# 20x20_adapter_rush_v2.net
KiCad netlist of a schematic drawn in EAGLE
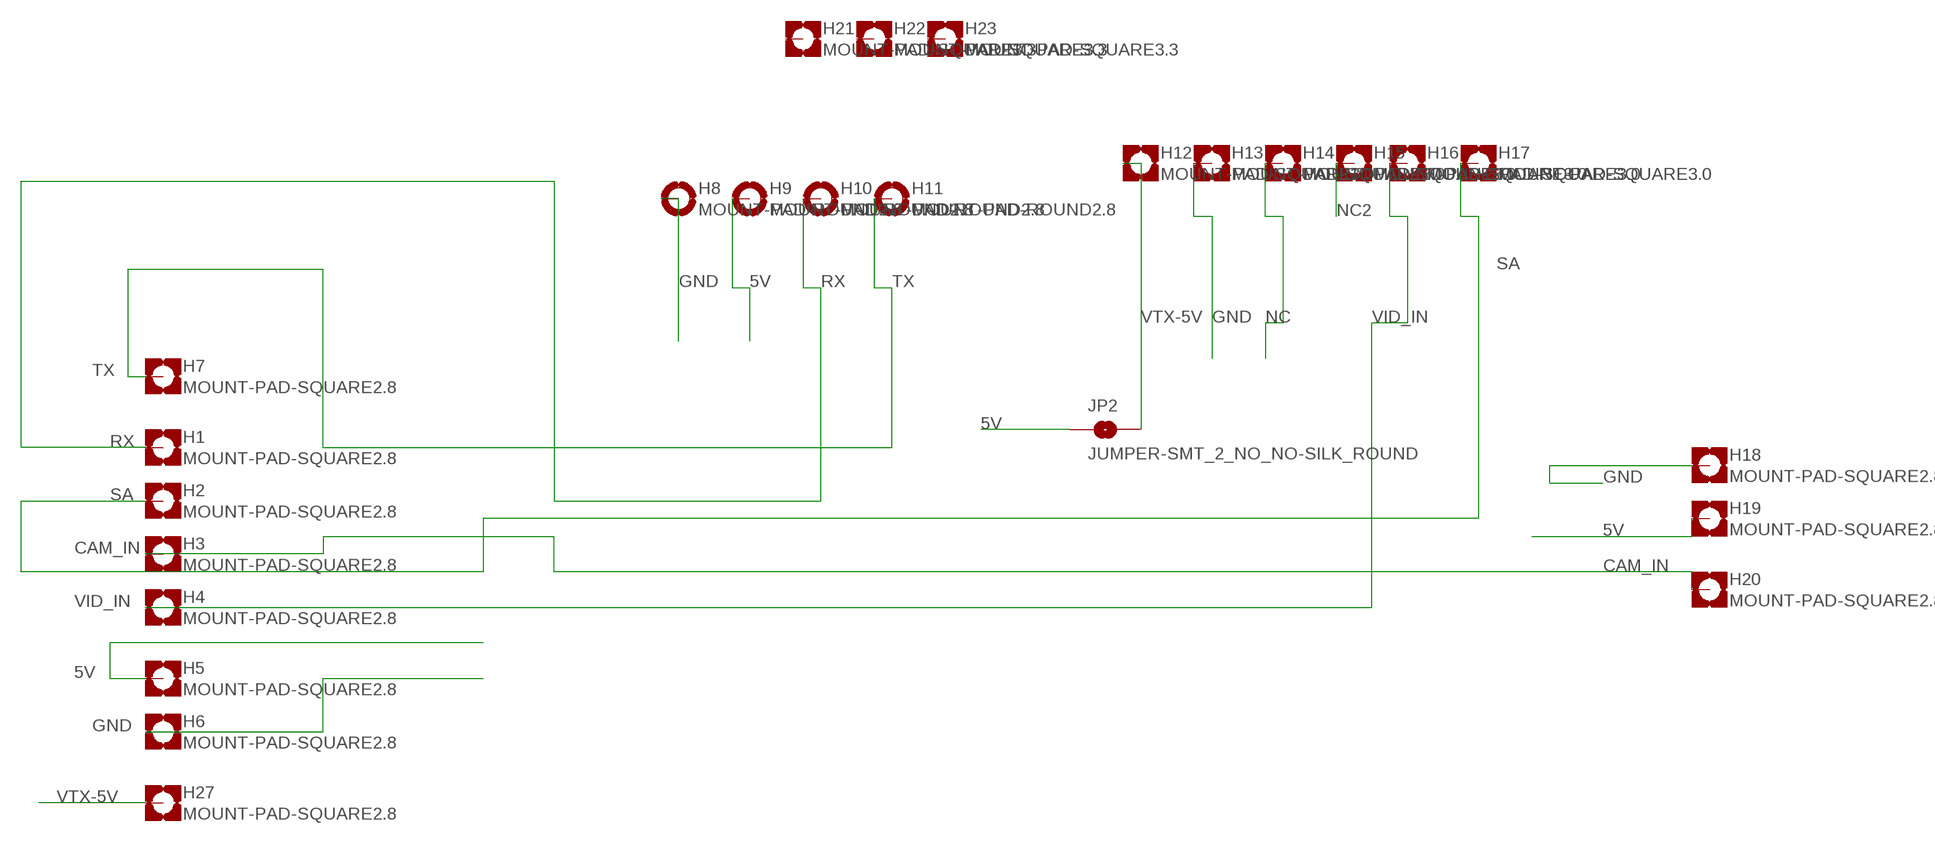
[diagram p0: schematic, sheet 1]

(export (version "E")
  (design (tool "Eeschema 10.0.6"))
  (components
    (comp (ref "H1")
      (value "MOUNT-PAD-SQUARE2.8")
      (footprint "eagle-import:2,8-PAD-SQUARE")
      (libsource (lib "eagle-import") (part "MOUNT-PAD-SQUARE2.8"))
    )
    (comp (ref "H2")
      (value "MOUNT-PAD-SQUARE2.8")
      (footprint "eagle-import:2,8-PAD-SQUARE")
      (libsource (lib "eagle-import") (part "MOUNT-PAD-SQUARE2.8"))
    )
    (comp (ref "H3")
      (value "MOUNT-PAD-SQUARE2.8")
      (footprint "eagle-import:2,8-PAD-SQUARE")
      (libsource (lib "eagle-import") (part "MOUNT-PAD-SQUARE2.8"))
    )
    (comp (ref "H4")
      (value "MOUNT-PAD-SQUARE2.8")
      (footprint "eagle-import:2,8-PAD-SQUARE")
      (libsource (lib "eagle-import") (part "MOUNT-PAD-SQUARE2.8"))
    )
    (comp (ref "H5")
      (value "MOUNT-PAD-SQUARE2.8")
      (footprint "eagle-import:2,8-PAD-SQUARE")
      (libsource (lib "eagle-import") (part "MOUNT-PAD-SQUARE2.8"))
    )
    (comp (ref "H6")
      (value "MOUNT-PAD-SQUARE2.8")
      (footprint "eagle-import:2,8-PAD-SQUARE")
      (libsource (lib "eagle-import") (part "MOUNT-PAD-SQUARE2.8"))
    )
    (comp (ref "H7")
      (value "MOUNT-PAD-SQUARE2.8")
      (footprint "eagle-import:2,8-PAD-SQUARE")
      (libsource (lib "eagle-import") (part "MOUNT-PAD-SQUARE2.8"))
    )
    (comp (ref "H8")
      (value "MOUNT-PAD-ROUND2.8")
      (footprint "eagle-import:1,0-PAD")
      (libsource (lib "eagle-import") (part "MOUNT-PAD-ROUND2.8"))
    )
    (comp (ref "H9")
      (value "MOUNT-PAD-ROUND2.8")
      (footprint "eagle-import:1,0-PAD")
      (libsource (lib "eagle-import") (part "MOUNT-PAD-ROUND2.8"))
    )
    (comp (ref "H10")
      (value "MOUNT-PAD-ROUND2.8")
      (footprint "eagle-import:1,0-PAD")
      (libsource (lib "eagle-import") (part "MOUNT-PAD-ROUND2.8"))
    )
    (comp (ref "H11")
      (value "MOUNT-PAD-ROUND2.8")
      (footprint "eagle-import:1,0-PAD")
      (libsource (lib "eagle-import") (part "MOUNT-PAD-ROUND2.8"))
    )
    (comp (ref "H12")
      (value "MOUNT-PAD-SQUARE3.0")
      (footprint "eagle-import:1,5-PAD-SQUARE")
      (libsource (lib "eagle-import") (part "MOUNT-PAD-SQUARE3.0"))
    )
    (comp (ref "H13")
      (value "MOUNT-PAD-SQUARE3.0")
      (footprint "eagle-import:1,5-PAD-SQUARE")
      (libsource (lib "eagle-import") (part "MOUNT-PAD-SQUARE3.0"))
    )
    (comp (ref "H14")
      (value "MOUNT-PAD-SQUARE3.0")
      (footprint "eagle-import:1,5-PAD-SQUARE")
      (libsource (lib "eagle-import") (part "MOUNT-PAD-SQUARE3.0"))
    )
    (comp (ref "H15")
      (value "MOUNT-PAD-SQUARE3.0")
      (footprint "eagle-import:1,5-PAD-SQUARE")
      (libsource (lib "eagle-import") (part "MOUNT-PAD-SQUARE3.0"))
    )
    (comp (ref "H16")
      (value "MOUNT-PAD-SQUARE3.0")
      (footprint "eagle-import:1,5-PAD-SQUARE")
      (libsource (lib "eagle-import") (part "MOUNT-PAD-SQUARE3.0"))
    )
    (comp (ref "H17")
      (value "MOUNT-PAD-SQUARE3.0")
      (footprint "eagle-import:1,5-PAD-SQUARE")
      (libsource (lib "eagle-import") (part "MOUNT-PAD-SQUARE3.0"))
    )
    (comp (ref "H18")
      (value "MOUNT-PAD-SQUARE2.8")
      (footprint "eagle-import:2,8-PAD-SQUARE")
      (libsource (lib "eagle-import") (part "MOUNT-PAD-SQUARE2.8"))
    )
    (comp (ref "H19")
      (value "MOUNT-PAD-SQUARE2.8")
      (footprint "eagle-import:2,8-PAD-SQUARE")
      (libsource (lib "eagle-import") (part "MOUNT-PAD-SQUARE2.8"))
    )
    (comp (ref "H20")
      (value "MOUNT-PAD-SQUARE2.8")
      (footprint "eagle-import:2,8-PAD-SQUARE")
      (libsource (lib "eagle-import") (part "MOUNT-PAD-SQUARE2.8"))
    )
    (comp (ref "H21")
      (value "MOUNT-PAD-SQUARE3.3")
      (footprint "eagle-import:3,3-PAD-SQUARE")
      (libsource (lib "eagle-import") (part "MOUNT-PAD-SQUARE3.3"))
    )
    (comp (ref "H22")
      (value "MOUNT-PAD-SQUARE3.3")
      (footprint "eagle-import:3,3-PAD-SQUARE")
      (libsource (lib "eagle-import") (part "MOUNT-PAD-SQUARE3.3"))
    )
    (comp (ref "H23")
      (value "MOUNT-PAD-SQUARE3.3")
      (footprint "eagle-import:3,3-PAD-SQUARE")
      (libsource (lib "eagle-import") (part "MOUNT-PAD-SQUARE3.3"))
    )
    (comp (ref "H27")
      (value "MOUNT-PAD-SQUARE2.8")
      (footprint "eagle-import:2,8-PAD-SQUARE")
      (libsource (lib "eagle-import") (part "MOUNT-PAD-SQUARE2.8"))
    )
    (comp (ref "JP2")
      (value "JUMPER-SMT_2_NO_NO-SILK_ROUND")
      (footprint "eagle-import:SMT-JUMPER_2_NO_NO-SILK_ROUND")
      (libsource (lib "eagle-import") (part "JUMPER-SMT_2_NO_NO-SILK_ROUND"))
    )
  )
  (nets
    (net (code "1") (name "/5V") (class "Default")
      (node (ref "H19") (pin "P$2") (pinfunction "MOUNT_P$2") (pintype "passive"))
      (node (ref "H5") (pin "P$2") (pinfunction "MOUNT_P$2") (pintype "passive"))
      (node (ref "H9") (pin "B1,0") (pinfunction "MOUNT_B1,0") (pintype "passive"))
      (node (ref "JP2") (pin "1") (pinfunction "1_1") (pintype "passive"))
    )
    (net (code "2") (name "/CAM_IN") (class "Default")
      (node (ref "H20") (pin "P$2") (pinfunction "MOUNT_P$2") (pintype "passive"))
      (node (ref "H3") (pin "P$2") (pinfunction "MOUNT_P$2") (pintype "passive"))
    )
    (net (code "3") (name "/GND") (class "Default")
      (node (ref "H13") (pin "P$1") (pinfunction "MOUNT_P$1") (pintype "passive"))
      (node (ref "H18") (pin "P$2") (pinfunction "MOUNT_P$2") (pintype "passive"))
      (node (ref "H6") (pin "P$2") (pinfunction "MOUNT_P$2") (pintype "passive"))
      (node (ref "H8") (pin "B1,0") (pinfunction "MOUNT_B1,0") (pintype "passive"))
    )
    (net (code "4") (name "/NC") (class "Default")
      (node (ref "H14") (pin "P$1") (pinfunction "MOUNT_P$1") (pintype "passive"))
    )
    (net (code "5") (name "/NC2") (class "Default")
      (node (ref "H15") (pin "P$1") (pinfunction "MOUNT_P$1") (pintype "passive"))
    )
    (net (code "6") (name "/RX") (class "Default")
      (node (ref "H1") (pin "P$2") (pinfunction "MOUNT_P$2") (pintype "passive"))
      (node (ref "H10") (pin "B1,0") (pinfunction "MOUNT_B1,0") (pintype "passive"))
    )
    (net (code "7") (name "/SA") (class "Default")
      (node (ref "H17") (pin "P$1") (pinfunction "MOUNT_P$1") (pintype "passive"))
      (node (ref "H2") (pin "P$2") (pinfunction "MOUNT_P$2") (pintype "passive"))
    )
    (net (code "8") (name "/TX") (class "Default")
      (node (ref "H11") (pin "B1,0") (pinfunction "MOUNT_B1,0") (pintype "passive"))
      (node (ref "H7") (pin "P$2") (pinfunction "MOUNT_P$2") (pintype "passive"))
    )
    (net (code "9") (name "/VID_IN") (class "Default")
      (node (ref "H16") (pin "P$1") (pinfunction "MOUNT_P$1") (pintype "passive"))
      (node (ref "H4") (pin "P$2") (pinfunction "MOUNT_P$2") (pintype "passive"))
    )
    (net (code "10") (name "/VTX-5V") (class "Default")
      (node (ref "H12") (pin "P$1") (pinfunction "MOUNT_P$1") (pintype "passive"))
      (node (ref "H27") (pin "P$2") (pinfunction "MOUNT_P$2") (pintype "passive"))
      (node (ref "JP2") (pin "2") (pinfunction "2_2") (pintype "passive"))
    )
    (net (code "11") (name "unconnected-(H21-MOUNT-PadP$1)") (class "Default")
      (node (ref "H21") (pin "P$1") (pinfunction "MOUNT_P$1") (pintype "passive"))
    )
    (net (code "12") (name "unconnected-(H22-MOUNT-PadP$1)") (class "Default")
      (node (ref "H22") (pin "P$1") (pinfunction "MOUNT_P$1") (pintype "passive"))
    )
    (net (code "13") (name "unconnected-(H23-MOUNT-PadP$1)") (class "Default")
      (node (ref "H23") (pin "P$1") (pinfunction "MOUNT_P$1") (pintype "passive"))
    )
  )
)
